# heater.net
KiCad netlist of a schematic drawn in EAGLE
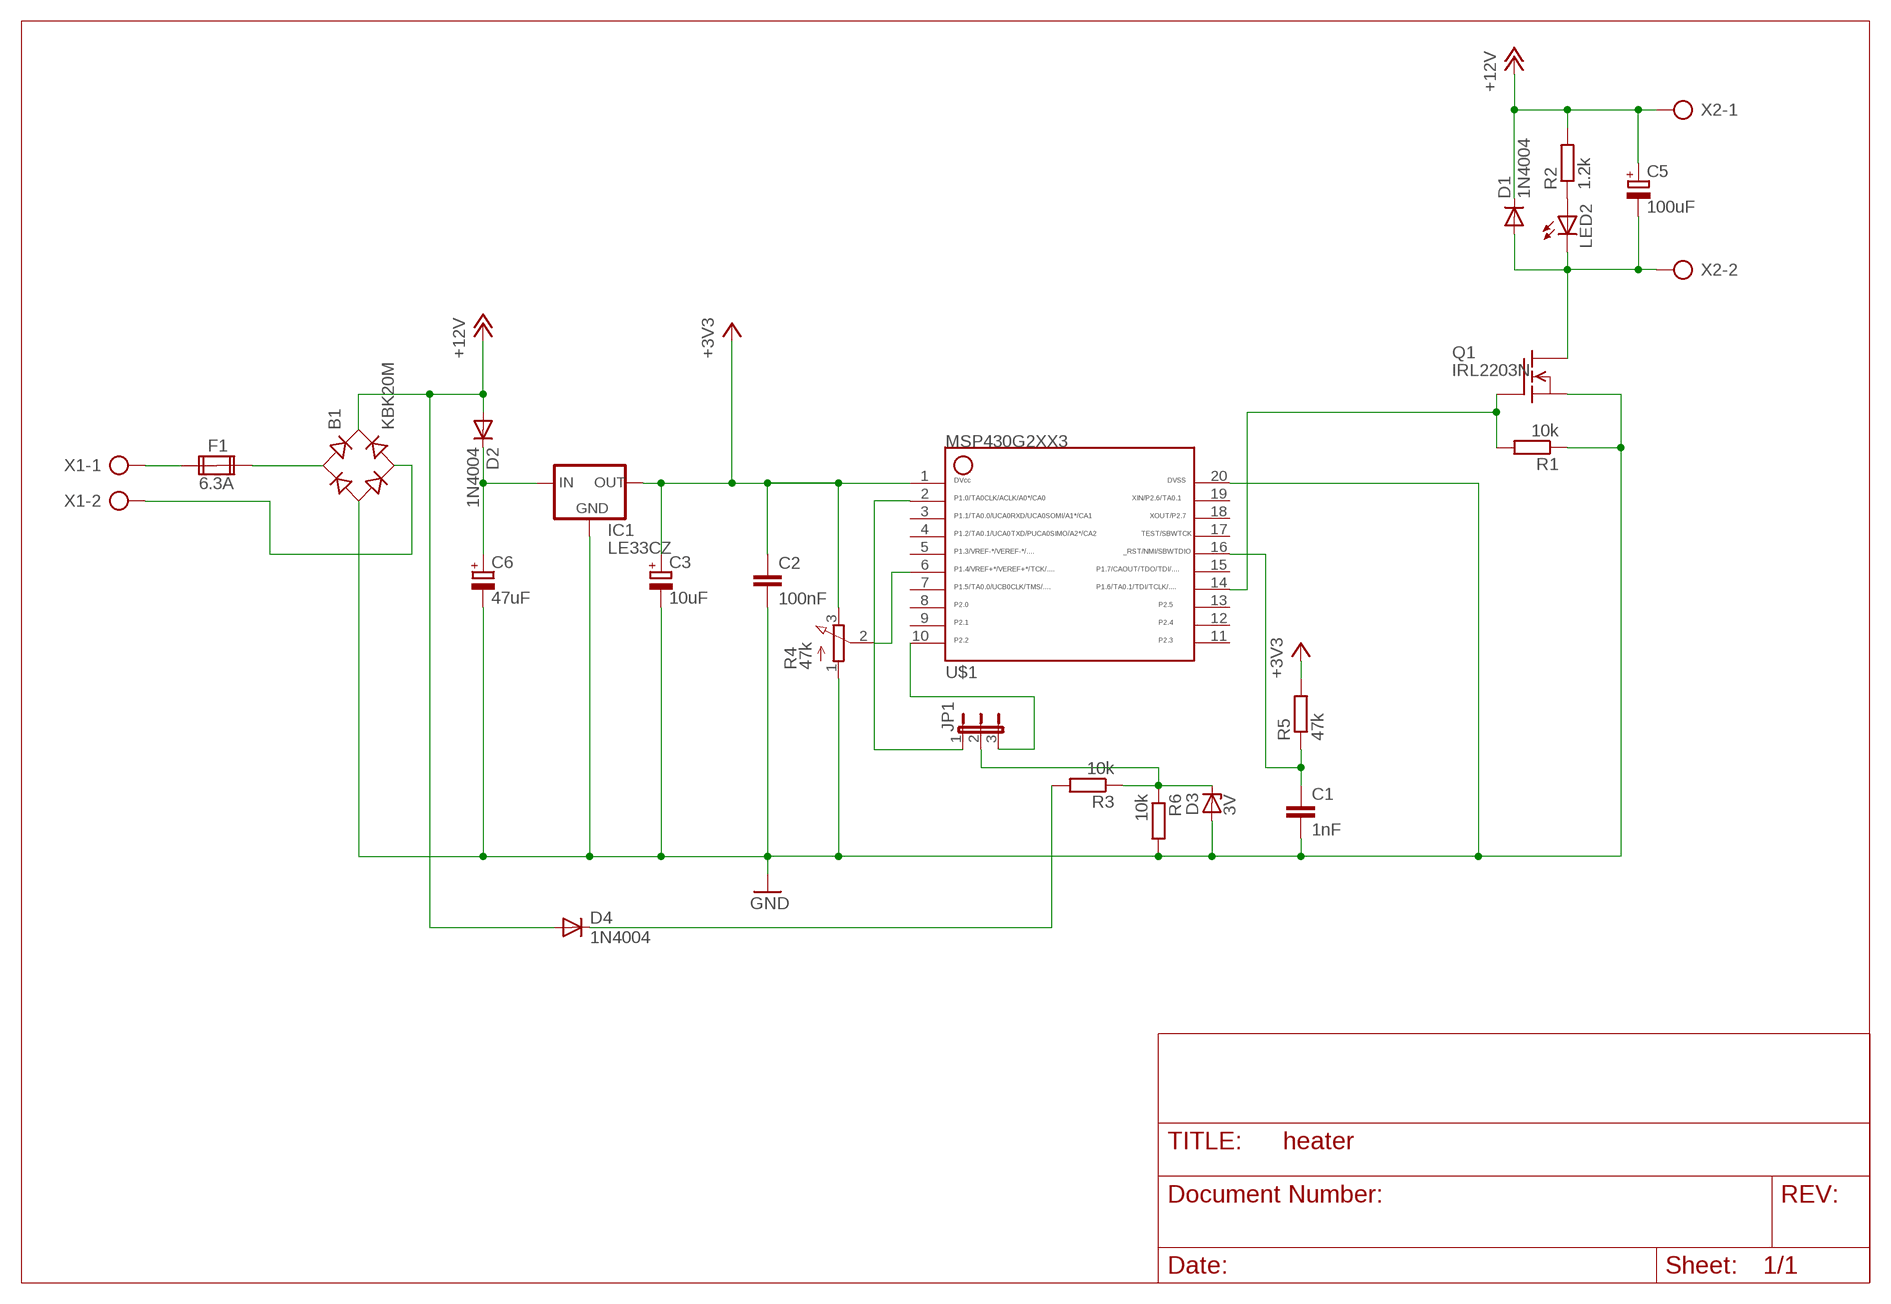
[diagram p0: schematic, sheet 1]

(export (version "E")
  (design (tool "Eeschema 10.0.6"))
  (components
    (comp (ref "B1")
      (value "KBK20M")
      (footprint "eagle-import:SKB32")
      (libsource (lib "eagle-import") (part "RECTIFIER-SKB32"))
    )
    (comp (ref "C1")
      (value "1nF")
      (footprint "eagle-import:C050-024X044")
      (libsource (lib "eagle-import") (part "C-EU050-024X044"))
    )
    (comp (ref "C2")
      (value "100nF")
      (footprint "eagle-import:C050-024X044")
      (libsource (lib "eagle-import") (part "C-EU050-024X044"))
    )
    (comp (ref "C3")
      (value "10uF")
      (footprint "eagle-import:E2,5-6E")
      (libsource (lib "eagle-import") (part "CPOL-EUE2,5-6E"))
    )
    (comp (ref "C5")
      (value "100uF")
      (footprint "eagle-import:E2,5-6E")
      (libsource (lib "eagle-import") (part "CPOL-EUE2,5-6E"))
    )
    (comp (ref "C6")
      (value "47uF")
      (footprint "eagle-import:E2,5-6E")
      (libsource (lib "eagle-import") (part "CPOL-EUE2,5-6E"))
    )
    (comp (ref "D1")
      (value "1N4004")
      (footprint "eagle-import:DO41-10")
      (libsource (lib "eagle-import") (part "1N4004"))
    )
    (comp (ref "D2")
      (value "1N4004")
      (footprint "eagle-import:DO41-10")
      (libsource (lib "eagle-import") (part "1N4004"))
    )
    (comp (ref "D3")
      (value "3V")
      (footprint "eagle-import:DO35Z10")
      (libsource (lib "eagle-import") (part "ZENER-DIODEDO35Z10"))
    )
    (comp (ref "D4")
      (value "1N4004")
      (footprint "eagle-import:DO41-10")
      (libsource (lib "eagle-import") (part "1N4004"))
    )
    (comp (ref "F1")
      (value "6.3A")
      (footprint "eagle-import:FUSE1")
      (libsource (lib "eagle-import") (part "FUSE2P"))
    )
    (comp (ref "IC1")
      (value "LE33CZ")
      (footprint "eagle-import:TO92")
      (libsource (lib "eagle-import") (part "LP2950?ACZ-3.3"))
    )
    (comp (ref "JP1")
      (value "JP2W")
      (footprint "eagle-import:JP2W")
      (libsource (lib "eagle-import") (part "JP2W"))
    )
    (comp (ref "LED2")
      (value "LED5MM")
      (footprint "eagle-import:LED5MM")
      (libsource (lib "eagle-import") (part "LED5MM"))
    )
    (comp (ref "Q1")
      (value "IRL2203N")
      (footprint "eagle-import:TO220")
      (libsource (lib "eagle-import") (part "IRF540"))
    )
    (comp (ref "R1")
      (value "10k")
      (footprint "eagle-import:0207_10")
      (libsource (lib "eagle-import") (part "R-EU_0207/10"))
    )
    (comp (ref "R2")
      (value "1.2k")
      (footprint "eagle-import:0207_10")
      (libsource (lib "eagle-import") (part "R-EU_0207/10"))
    )
    (comp (ref "R3")
      (value "10k")
      (footprint "eagle-import:0207_10")
      (libsource (lib "eagle-import") (part "R-EU_0207/10"))
    )
    (comp (ref "R4")
      (value "47k")
      (footprint "eagle-import:3RP_1610N")
      (libsource (lib "eagle-import") (part "3RP/1610N"))
    )
    (comp (ref "R5")
      (value "47k")
      (footprint "eagle-import:0207_10")
      (libsource (lib "eagle-import") (part "R-EU_0207/10"))
    )
    (comp (ref "R6")
      (value "10k")
      (footprint "eagle-import:0207_10")
      (libsource (lib "eagle-import") (part "R-EU_0207/10"))
    )
    (comp (ref "U$1")
      (value "MSP430G2533")
      (footprint "eagle-import:N20")
      (libsource (lib "eagle-import") (part "G2XX3---N20"))
    )
    (comp (ref "X1")
      (value "AK500/2")
      (footprint "eagle-import:AK500_2")
      (libsource (lib "eagle-import") (part "AK500/2"))
    )
    (comp (ref "X2")
      (value "AK500/2")
      (footprint "eagle-import:AK500_2")
      (libsource (lib "eagle-import") (part "AK500/2"))
    )
  )
  (nets
    (net (code "1") (name "+3V3") (class "Default")
      (node (ref "C2") (pin "1") (pinfunction "1_1") (pintype "passive"))
      (node (ref "C3") (pin "+") (pinfunction "+_+") (pintype "passive"))
      (node (ref "IC1") (pin "1") (pinfunction "OUT_1") (pintype "passive"))
      (node (ref "R4") (pin "3") (pinfunction "E_3") (pintype "passive"))
      (node (ref "R5") (pin "2") (pinfunction "2_2") (pintype "passive"))
      (node (ref "U$1") (pin "1") (pinfunction "1_1") (pintype "bidirectional"))
    )
    (net (code "2") (name "+12V") (class "Default")
      (node (ref "B1") (pin "+") (pinfunction "+_+") (pintype "passive"))
      (node (ref "C5") (pin "+") (pinfunction "+_+") (pintype "passive"))
      (node (ref "D1") (pin "C") (pinfunction "C_C") (pintype "passive"))
      (node (ref "D2") (pin "A") (pinfunction "A_A") (pintype "passive"))
      (node (ref "D4") (pin "A") (pinfunction "A_A") (pintype "passive"))
      (node (ref "R2") (pin "2") (pinfunction "2_2") (pintype "passive"))
      (node (ref "X2") (pin "1") (pinfunction "KL_1") (pintype "passive"))
    )
    (net (code "3") (name "GND") (class "Default")
      (node (ref "B1") (pin "-") (pinfunction "-_-") (pintype "passive"))
      (node (ref "C1") (pin "2") (pinfunction "2_2") (pintype "passive"))
      (node (ref "C2") (pin "2") (pinfunction "2_2") (pintype "passive"))
      (node (ref "C3") (pin "-") (pinfunction "-_-") (pintype "passive"))
      (node (ref "C6") (pin "-") (pinfunction "-_-") (pintype "passive"))
      (node (ref "D3") (pin "A") (pinfunction "A_A") (pintype "passive"))
      (node (ref "IC1") (pin "2") (pinfunction "GND_2") (pintype "input"))
      (node (ref "Q1") (pin "3") (pinfunction "S_3") (pintype "passive"))
      (node (ref "R1") (pin "1") (pinfunction "1_1") (pintype "passive"))
      (node (ref "R4") (pin "1") (pinfunction "A_1") (pintype "passive"))
      (node (ref "R6") (pin "2") (pinfunction "2_2") (pintype "passive"))
      (node (ref "U$1") (pin "20") (pinfunction "20_20") (pintype "bidirectional"))
    )
    (net (code "4") (name "Net-(B1-PadAC1)") (class "Default")
      (node (ref "B1") (pin "AC1") (pinfunction "AC1_AC1") (pintype "passive"))
      (node (ref "F1") (pin "2A") (pinfunction "2A_2A") (pintype "passive"))
    )
    (net (code "5") (name "Net-(C1-Pad1)") (class "Default")
      (node (ref "C1") (pin "1") (pinfunction "1_1") (pintype "passive"))
      (node (ref "R5") (pin "1") (pinfunction "1_1") (pintype "passive"))
      (node (ref "U$1") (pin "16") (pinfunction "16_16") (pintype "bidirectional"))
    )
    (net (code "6") (name "Net-(D3-PadC)") (class "Default")
      (node (ref "D3") (pin "C") (pinfunction "C_C") (pintype "passive"))
      (node (ref "JP1") (pin "2") (pinfunction "2_2") (pintype "passive"))
      (node (ref "R3") (pin "1") (pinfunction "1_1") (pintype "passive"))
      (node (ref "R6") (pin "1") (pinfunction "1_1") (pintype "passive"))
    )
    (net (code "7") (name "Net-(D4-PadC)") (class "Default")
      (node (ref "D4") (pin "C") (pinfunction "C_C") (pintype "passive"))
      (node (ref "R3") (pin "2") (pinfunction "2_2") (pintype "passive"))
    )
    (net (code "8") (name "Net-(IC1-IN)") (class "Default")
      (node (ref "C6") (pin "+") (pinfunction "+_+") (pintype "passive"))
      (node (ref "D2") (pin "C") (pinfunction "C_C") (pintype "passive"))
      (node (ref "IC1") (pin "3") (pinfunction "IN_3") (pintype "input"))
    )
    (net (code "9") (name "Net-(JP1-Pad1)") (class "Default")
      (node (ref "JP1") (pin "1") (pinfunction "1_1") (pintype "passive"))
      (node (ref "U$1") (pin "2") (pinfunction "2_2") (pintype "bidirectional"))
    )
    (net (code "10") (name "Net-(JP1-Pad3)") (class "Default")
      (node (ref "JP1") (pin "3") (pinfunction "3_3") (pintype "passive"))
      (node (ref "U$1") (pin "10") (pinfunction "10_10") (pintype "bidirectional"))
    )
    (net (code "11") (name "Net-(LED2-C)") (class "Default")
      (node (ref "C5") (pin "-") (pinfunction "-_-") (pintype "passive"))
      (node (ref "D1") (pin "A") (pinfunction "A_A") (pintype "passive"))
      (node (ref "LED2") (pin "K") (pinfunction "C_K") (pintype "passive"))
      (node (ref "Q1") (pin "2") (pinfunction "D_2") (pintype "passive"))
      (node (ref "X2") (pin "2") (pinfunction "KL_2") (pintype "passive"))
    )
    (net (code "12") (name "Net-(LED2-PadA)") (class "Default")
      (node (ref "LED2") (pin "A") (pinfunction "A_A") (pintype "passive"))
      (node (ref "R2") (pin "1") (pinfunction "1_1") (pintype "passive"))
    )
    (net (code "13") (name "Net-(Q1-G)") (class "Default")
      (node (ref "Q1") (pin "1") (pinfunction "G_1") (pintype "passive"))
      (node (ref "R1") (pin "2") (pinfunction "2_2") (pintype "passive"))
      (node (ref "U$1") (pin "14") (pinfunction "14_14") (pintype "bidirectional"))
    )
    (net (code "14") (name "Net-(R4-S)") (class "Default")
      (node (ref "R4") (pin "2") (pinfunction "S_2") (pintype "passive"))
      (node (ref "U$1") (pin "6") (pinfunction "6_6") (pintype "bidirectional"))
    )
    (net (code "15") (name "Net-(X1A-KL)") (class "Default")
      (node (ref "F1") (pin "1A") (pinfunction "1A_1A") (pintype "passive"))
      (node (ref "X1") (pin "1") (pinfunction "KL_1") (pintype "passive"))
    )
    (net (code "16") (name "Net-(X1B-KL)") (class "Default")
      (node (ref "B1") (pin "AC2") (pinfunction "AC2_AC2") (pintype "passive"))
      (node (ref "X1") (pin "2") (pinfunction "KL_2") (pintype "passive"))
    )
    (net (code "17") (name "unconnected-(F1-Pad1B)") (class "Default")
      (node (ref "F1") (pin "1B") (pinfunction "1B_1B") (pintype "passive"))
    )
    (net (code "18") (name "unconnected-(F1-Pad2B)") (class "Default")
      (node (ref "F1") (pin "2B") (pinfunction "2B_2B") (pintype "passive"))
    )
    (net (code "19") (name "unconnected-(U$1-Pad3)") (class "Default")
      (node (ref "U$1") (pin "3") (pinfunction "3_3") (pintype "bidirectional"))
    )
    (net (code "20") (name "unconnected-(U$1-Pad4)") (class "Default")
      (node (ref "U$1") (pin "4") (pinfunction "4_4") (pintype "bidirectional"))
    )
    (net (code "21") (name "unconnected-(U$1-Pad5)") (class "Default")
      (node (ref "U$1") (pin "5") (pinfunction "5_5") (pintype "bidirectional"))
    )
    (net (code "22") (name "unconnected-(U$1-Pad7)") (class "Default")
      (node (ref "U$1") (pin "7") (pinfunction "7_7") (pintype "bidirectional"))
    )
    (net (code "23") (name "unconnected-(U$1-Pad8)") (class "Default")
      (node (ref "U$1") (pin "8") (pinfunction "8_8") (pintype "bidirectional"))
    )
    (net (code "24") (name "unconnected-(U$1-Pad9)") (class "Default")
      (node (ref "U$1") (pin "9") (pinfunction "9_9") (pintype "bidirectional"))
    )
    (net (code "25") (name "unconnected-(U$1-Pad11)") (class "Default")
      (node (ref "U$1") (pin "11") (pinfunction "11_11") (pintype "bidirectional"))
    )
    (net (code "26") (name "unconnected-(U$1-Pad12)") (class "Default")
      (node (ref "U$1") (pin "12") (pinfunction "12_12") (pintype "bidirectional"))
    )
    (net (code "27") (name "unconnected-(U$1-Pad13)") (class "Default")
      (node (ref "U$1") (pin "13") (pinfunction "13_13") (pintype "bidirectional"))
    )
    (net (code "28") (name "unconnected-(U$1-Pad15)") (class "Default")
      (node (ref "U$1") (pin "15") (pinfunction "15_15") (pintype "bidirectional"))
    )
    (net (code "29") (name "unconnected-(U$1-Pad17)") (class "Default")
      (node (ref "U$1") (pin "17") (pinfunction "17_17") (pintype "bidirectional"))
    )
    (net (code "30") (name "unconnected-(U$1-Pad18)") (class "Default")
      (node (ref "U$1") (pin "18") (pinfunction "18_18") (pintype "bidirectional"))
    )
    (net (code "31") (name "unconnected-(U$1-Pad19)") (class "Default")
      (node (ref "U$1") (pin "19") (pinfunction "19_19") (pintype "bidirectional"))
    )
  )
)
